# dc_dc.net
KiCad netlist of a schematic drawn in EAGLE
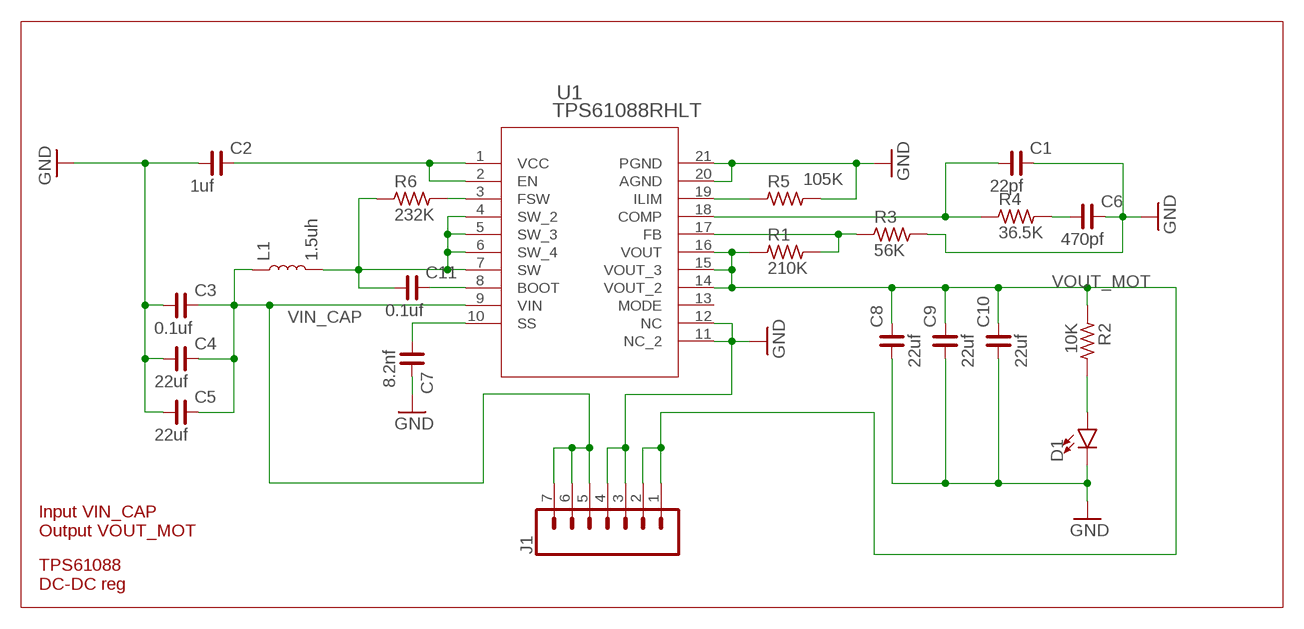
[diagram p0: schematic, sheet 1]

(export (version "E")
  (design (tool "Eeschema 10.0.6"))
  (components
    (comp (ref "C1")
      (value "22pf")
      (footprint "eagle-import:C0603")
      (libsource (lib "eagle-import") (part "C_0603"))
    )
    (comp (ref "C2")
      (value "1uf")
      (footprint "eagle-import:C0603")
      (libsource (lib "eagle-import") (part "C_0603"))
    )
    (comp (ref "C3")
      (value "0.1uf")
      (footprint "eagle-import:C0603")
      (libsource (lib "eagle-import") (part "C_0603"))
    )
    (comp (ref "C4")
      (value "22uf")
      (footprint "eagle-import:C1210")
      (libsource (lib "eagle-import") (part "C_1210"))
    )
    (comp (ref "C5")
      (value "22uf")
      (footprint "eagle-import:C1210")
      (libsource (lib "eagle-import") (part "C_1210"))
    )
    (comp (ref "C6")
      (value "470pf")
      (footprint "eagle-import:C0603")
      (libsource (lib "eagle-import") (part "C_0603"))
    )
    (comp (ref "C7")
      (value "8.2nf")
      (footprint "eagle-import:C0603")
      (libsource (lib "eagle-import") (part "C_0603"))
    )
    (comp (ref "C8")
      (value "22uf")
      (footprint "eagle-import:C1210")
      (libsource (lib "eagle-import") (part "C_1210"))
    )
    (comp (ref "C9")
      (value "22uf")
      (footprint "eagle-import:C1210")
      (libsource (lib "eagle-import") (part "C_1210"))
    )
    (comp (ref "C10")
      (value "22uf")
      (footprint "eagle-import:C1210")
      (libsource (lib "eagle-import") (part "C_1210"))
    )
    (comp (ref "C11")
      (value "0.1uf")
      (footprint "eagle-import:C0603")
      (libsource (lib "eagle-import") (part "C_0603"))
    )
    (comp (ref "D1")
      (value "LED0603")
      (footprint "eagle-import:LED-0603")
      (libsource (lib "eagle-import") (part "LED0603"))
    )
    (comp (ref "J1")
      (value "CONN_07LONGPADS")
      (footprint "eagle-import:1X07_LONGPADS")
      (libsource (lib "eagle-import") (part "CONN_07LONGPADS"))
    )
    (comp (ref "L1")
      (value "1.5uh")
      (footprint "eagle-import:CR75")
      (libsource (lib "eagle-import") (part "INDUCTOR-CR75-68UH"))
    )
    (comp (ref "R1")
      (value "210K")
      (footprint "eagle-import:R0603")
      (libsource (lib "eagle-import") (part "R_0603"))
    )
    (comp (ref "R2")
      (value "10K")
      (footprint "eagle-import:R0603")
      (libsource (lib "eagle-import") (part "R_0603"))
    )
    (comp (ref "R3")
      (value "56K")
      (footprint "eagle-import:R0603")
      (libsource (lib "eagle-import") (part "R_0603"))
    )
    (comp (ref "R4")
      (value "36.5K")
      (footprint "eagle-import:R0603")
      (libsource (lib "eagle-import") (part "R_0603"))
    )
    (comp (ref "R5")
      (value "105K")
      (footprint "eagle-import:R0603")
      (libsource (lib "eagle-import") (part "R_0603"))
    )
    (comp (ref "R6")
      (value "232K")
      (footprint "eagle-import:R0603")
      (libsource (lib "eagle-import") (part "R_0603"))
    )
    (comp (ref "U1")
      (value "TPS61088RHLT")
      (footprint "eagle-import:RHL0020A_TEX")
      (fields (field (name "COPYRIGHT") "Copyright (C) 2018 Accelerated Designs. All rights reserved"))
      (libsource (lib "eagle-import") (part "TPS61088RHLT"))
    )
  )
  (nets
    (net (code "1") (name "/VIN_CAP") (class "Default")
      (node (ref "C3") (pin "2") (pinfunction "2_2") (pintype "passive"))
      (node (ref "C4") (pin "2") (pinfunction "2_2") (pintype "passive"))
      (node (ref "C5") (pin "2") (pinfunction "2_2") (pintype "passive"))
      (node (ref "J1") (pin "5") (pinfunction "5_5") (pintype "passive"))
      (node (ref "J1") (pin "6") (pinfunction "6_6") (pintype "passive"))
      (node (ref "J1") (pin "7") (pinfunction "7_7") (pintype "passive"))
      (node (ref "L1") (pin "P$1") (pinfunction "1_P$1") (pintype "passive"))
      (node (ref "U1") (pin "9") (pinfunction "VIN_9") (pintype "power_in"))
    )
    (net (code "2") (name "/VOUT_MOT") (class "Default")
      (node (ref "C10") (pin "2") (pinfunction "2_2") (pintype "passive"))
      (node (ref "C8") (pin "2") (pinfunction "2_2") (pintype "passive"))
      (node (ref "C9") (pin "2") (pinfunction "2_2") (pintype "passive"))
      (node (ref "J1") (pin "1") (pinfunction "1_1") (pintype "passive"))
      (node (ref "J1") (pin "2") (pinfunction "2_2") (pintype "passive"))
      (node (ref "R1") (pin "1") (pinfunction "1_1") (pintype "passive"))
      (node (ref "R2") (pin "1") (pinfunction "1_1") (pintype "passive"))
      (node (ref "U1") (pin "14") (pinfunction "VOUT_2_14") (pintype "power_in"))
      (node (ref "U1") (pin "15") (pinfunction "VOUT_3_15") (pintype "power_in"))
      (node (ref "U1") (pin "16") (pinfunction "VOUT_16") (pintype "power_in"))
    )
    (net (code "3") (name "GND") (class "Default")
      (node (ref "C1") (pin "2") (pinfunction "2_2") (pintype "passive"))
      (node (ref "C10") (pin "1") (pinfunction "1_1") (pintype "passive"))
      (node (ref "C2") (pin "1") (pinfunction "1_1") (pintype "passive"))
      (node (ref "C3") (pin "1") (pinfunction "1_1") (pintype "passive"))
      (node (ref "C4") (pin "1") (pinfunction "1_1") (pintype "passive"))
      (node (ref "C5") (pin "1") (pinfunction "1_1") (pintype "passive"))
      (node (ref "C6") (pin "2") (pinfunction "2_2") (pintype "passive"))
      (node (ref "C7") (pin "2") (pinfunction "2_2") (pintype "passive"))
      (node (ref "C8") (pin "1") (pinfunction "1_1") (pintype "passive"))
      (node (ref "C9") (pin "1") (pinfunction "1_1") (pintype "passive"))
      (node (ref "D1") (pin "C") (pinfunction "C_C") (pintype "passive"))
      (node (ref "J1") (pin "3") (pinfunction "3_3") (pintype "passive"))
      (node (ref "J1") (pin "4") (pinfunction "4_4") (pintype "passive"))
      (node (ref "R3") (pin "2") (pinfunction "2_2") (pintype "passive"))
      (node (ref "R5") (pin "2") (pinfunction "2_2") (pintype "passive"))
      (node (ref "U1") (pin "11") (pinfunction "NC_2_11") (pintype "passive"))
      (node (ref "U1") (pin "12") (pinfunction "NC_12") (pintype "passive"))
      (node (ref "U1") (pin "20") (pinfunction "AGND_20") (pintype "power_in"))
      (node (ref "U1") (pin "21") (pinfunction "PGND_21") (pintype "power_in"))
    )
    (net (code "4") (name "Net-(C6-Pad1)") (class "Default")
      (node (ref "C6") (pin "1") (pinfunction "1_1") (pintype "passive"))
      (node (ref "R4") (pin "2") (pinfunction "2_2") (pintype "passive"))
    )
    (net (code "5") (name "Net-(D1-PadA)") (class "Default")
      (node (ref "D1") (pin "A") (pinfunction "A_A") (pintype "passive"))
      (node (ref "R2") (pin "2") (pinfunction "2_2") (pintype "passive"))
    )
    (net (code "6") (name "Net-(L1-2)") (class "Default")
      (node (ref "C11") (pin "1") (pinfunction "1_1") (pintype "passive"))
      (node (ref "L1") (pin "P$2") (pinfunction "2_P$2") (pintype "passive"))
      (node (ref "R6") (pin "1") (pinfunction "1_1") (pintype "passive"))
      (node (ref "U1") (pin "4") (pinfunction "SW_2_4") (pintype "power_in"))
      (node (ref "U1") (pin "5") (pinfunction "SW_3_5") (pintype "power_in"))
      (node (ref "U1") (pin "6") (pinfunction "SW_4_6") (pintype "power_in"))
      (node (ref "U1") (pin "7") (pinfunction "SW_7") (pintype "power_in"))
    )
    (net (code "7") (name "Net-(U1-BOOT)") (class "Default")
      (node (ref "C11") (pin "2") (pinfunction "2_2") (pintype "passive"))
      (node (ref "U1") (pin "8") (pinfunction "BOOT_8") (pintype "power_in"))
    )
    (net (code "8") (name "Net-(U1-COMP)") (class "Default")
      (node (ref "C1") (pin "1") (pinfunction "1_1") (pintype "passive"))
      (node (ref "R4") (pin "1") (pinfunction "1_1") (pintype "passive"))
      (node (ref "U1") (pin "18") (pinfunction "COMP_18") (pintype "output"))
    )
    (net (code "9") (name "Net-(U1-EN)") (class "Default")
      (node (ref "C2") (pin "2") (pinfunction "2_2") (pintype "passive"))
      (node (ref "U1") (pin "1") (pinfunction "VCC_1") (pintype "power_in"))
      (node (ref "U1") (pin "2") (pinfunction "EN_2") (pintype "input"))
    )
    (net (code "10") (name "Net-(U1-FB)") (class "Default")
      (node (ref "R1") (pin "2") (pinfunction "2_2") (pintype "passive"))
      (node (ref "R3") (pin "1") (pinfunction "1_1") (pintype "passive"))
      (node (ref "U1") (pin "17") (pinfunction "FB_17") (pintype "input"))
    )
    (net (code "11") (name "Net-(U1-FSW)") (class "Default")
      (node (ref "R6") (pin "2") (pinfunction "2_2") (pintype "passive"))
      (node (ref "U1") (pin "3") (pinfunction "FSW_3") (pintype "input"))
    )
    (net (code "12") (name "Net-(U1-ILIM)") (class "Default")
      (node (ref "R5") (pin "1") (pinfunction "1_1") (pintype "passive"))
      (node (ref "U1") (pin "19") (pinfunction "ILIM_19") (pintype "input"))
    )
    (net (code "13") (name "Net-(U1-SS)") (class "Default")
      (node (ref "C7") (pin "1") (pinfunction "1_1") (pintype "passive"))
      (node (ref "U1") (pin "10") (pinfunction "SS_10") (pintype "input"))
    )
    (net (code "14") (name "unconnected-(U1-MODE-Pad13)") (class "Default")
      (node (ref "U1") (pin "13") (pinfunction "MODE_13") (pintype "input"))
    )
  )
)
